# nocte-lux.net
KiCad netlist of a schematic drawn in EAGLE
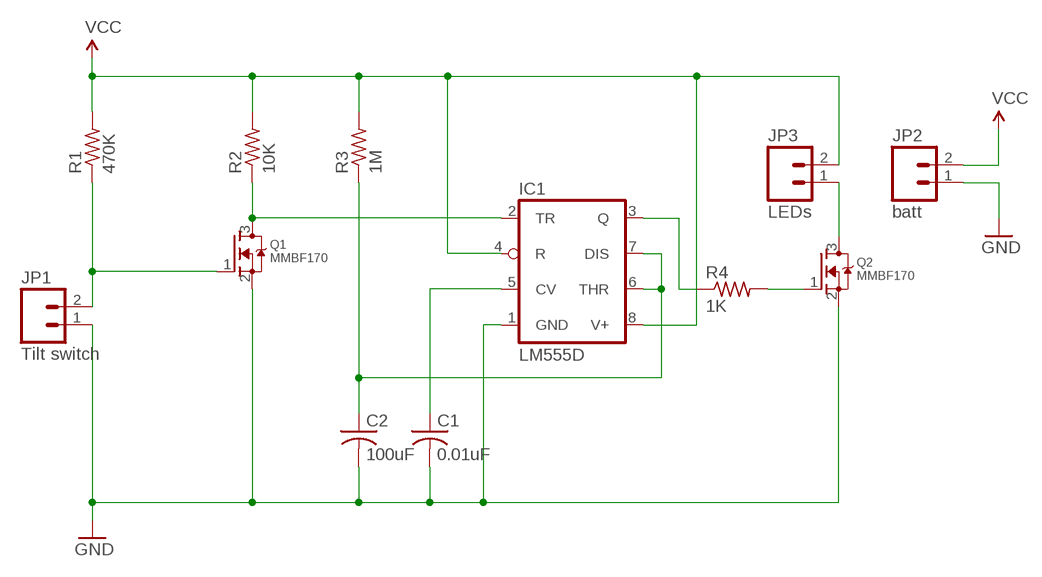
[diagram p0: schematic, sheet 1]

(export (version "E")
  (design (tool "Eeschema 10.0.6"))
  (components
    (comp (ref "C1")
      (value "0.01uF")
      (footprint "eagle-import:C1206")
      (libsource (lib "eagle-import") (part "C-USC1206"))
    )
    (comp (ref "C2")
      (value "100uF")
      (footprint "eagle-import:C1206")
      (libsource (lib "eagle-import") (part "C-USC1206"))
    )
    (comp (ref "IC1")
      (value "LM555D")
      (footprint "eagle-import:SO08")
      (libsource (lib "eagle-import") (part "555DLM"))
    )
    (comp (ref "JP1")
      (value "Tilt switch")
      (footprint "eagle-import:1X02")
      (libsource (lib "eagle-import") (part "M02PTH"))
    )
    (comp (ref "JP2")
      (value "batt")
      (footprint "eagle-import:1X02")
      (libsource (lib "eagle-import") (part "M02PTH"))
    )
    (comp (ref "JP3")
      (value "LEDs")
      (footprint "eagle-import:1X02")
      (libsource (lib "eagle-import") (part "M02PTH"))
    )
    (comp (ref "Q1")
      (value "MMBF170")
      (footprint "eagle-import:SOT23-W")
      (libsource (lib "eagle-import") (part "MOSFET-NWAVE"))
    )
    (comp (ref "Q2")
      (value "MMBF170")
      (footprint "eagle-import:SOT23-W")
      (libsource (lib "eagle-import") (part "MOSFET-NWAVE"))
    )
    (comp (ref "R1")
      (value "470K")
      (footprint "eagle-import:M1206")
      (libsource (lib "eagle-import") (part "R-US_M1206"))
    )
    (comp (ref "R2")
      (value "10K")
      (footprint "eagle-import:M1206")
      (libsource (lib "eagle-import") (part "R-US_M1206"))
    )
    (comp (ref "R3")
      (value "1M")
      (footprint "eagle-import:M1206")
      (libsource (lib "eagle-import") (part "R-US_M1206"))
    )
    (comp (ref "R4")
      (value "1K")
      (footprint "eagle-import:M1206")
      (libsource (lib "eagle-import") (part "R-US_M1206"))
    )
  )
  (nets
    (net (code "1") (name "GND") (class "Default")
      (node (ref "C1") (pin "2") (pinfunction "2_2") (pintype "passive"))
      (node (ref "C2") (pin "2") (pinfunction "2_2") (pintype "passive"))
      (node (ref "IC1") (pin "1") (pinfunction "GND_1") (pintype "power_in"))
      (node (ref "JP1") (pin "1") (pinfunction "1_1") (pintype "passive"))
      (node (ref "JP2") (pin "1") (pinfunction "1_1") (pintype "passive"))
      (node (ref "Q1") (pin "2") (pinfunction "S_2") (pintype "bidirectional"))
      (node (ref "Q2") (pin "2") (pinfunction "S_2") (pintype "bidirectional"))
    )
    (net (code "2") (name "Net-(IC1-CV)") (class "Default")
      (node (ref "C1") (pin "1") (pinfunction "1_1") (pintype "passive"))
      (node (ref "IC1") (pin "5") (pinfunction "CV_5") (pintype "input"))
    )
    (net (code "3") (name "Net-(IC1-DIS)") (class "Default")
      (node (ref "C2") (pin "1") (pinfunction "1_1") (pintype "passive"))
      (node (ref "IC1") (pin "6") (pinfunction "THR_6") (pintype "input"))
      (node (ref "IC1") (pin "7") (pinfunction "DIS_7") (pintype "input"))
      (node (ref "R3") (pin "1") (pinfunction "1_1") (pintype "passive"))
    )
    (net (code "4") (name "Net-(IC1-Q)") (class "Default")
      (node (ref "IC1") (pin "3") (pinfunction "Q_3") (pintype "output"))
      (node (ref "R4") (pin "1") (pinfunction "1_1") (pintype "passive"))
    )
    (net (code "5") (name "Net-(IC1-TR)") (class "Default")
      (node (ref "IC1") (pin "2") (pinfunction "TR_2") (pintype "input"))
      (node (ref "Q1") (pin "3") (pinfunction "D_3") (pintype "bidirectional"))
      (node (ref "R2") (pin "1") (pinfunction "1_1") (pintype "passive"))
    )
    (net (code "6") (name "Net-(Q1-G)") (class "Default")
      (node (ref "JP1") (pin "2") (pinfunction "2_2") (pintype "passive"))
      (node (ref "Q1") (pin "1") (pinfunction "G_1") (pintype "bidirectional"))
      (node (ref "R1") (pin "1") (pinfunction "1_1") (pintype "passive"))
    )
    (net (code "7") (name "Net-(Q2-D)") (class "Default")
      (node (ref "JP3") (pin "1") (pinfunction "1_1") (pintype "passive"))
      (node (ref "Q2") (pin "3") (pinfunction "D_3") (pintype "bidirectional"))
    )
    (net (code "8") (name "Net-(Q2-G)") (class "Default")
      (node (ref "Q2") (pin "1") (pinfunction "G_1") (pintype "bidirectional"))
      (node (ref "R4") (pin "2") (pinfunction "2_2") (pintype "passive"))
    )
    (net (code "9") (name "VCC") (class "Default")
      (node (ref "IC1") (pin "4") (pinfunction "R_4") (pintype "input"))
      (node (ref "IC1") (pin "8") (pinfunction "V+_8") (pintype "power_in"))
      (node (ref "JP2") (pin "2") (pinfunction "2_2") (pintype "passive"))
      (node (ref "JP3") (pin "2") (pinfunction "2_2") (pintype "passive"))
      (node (ref "R1") (pin "2") (pinfunction "2_2") (pintype "passive"))
      (node (ref "R2") (pin "2") (pinfunction "2_2") (pintype "passive"))
      (node (ref "R3") (pin "2") (pinfunction "2_2") (pintype "passive"))
    )
  )
)
